# Sheet1.net
KiCad netlist of a schematic drawn in Altium Designer
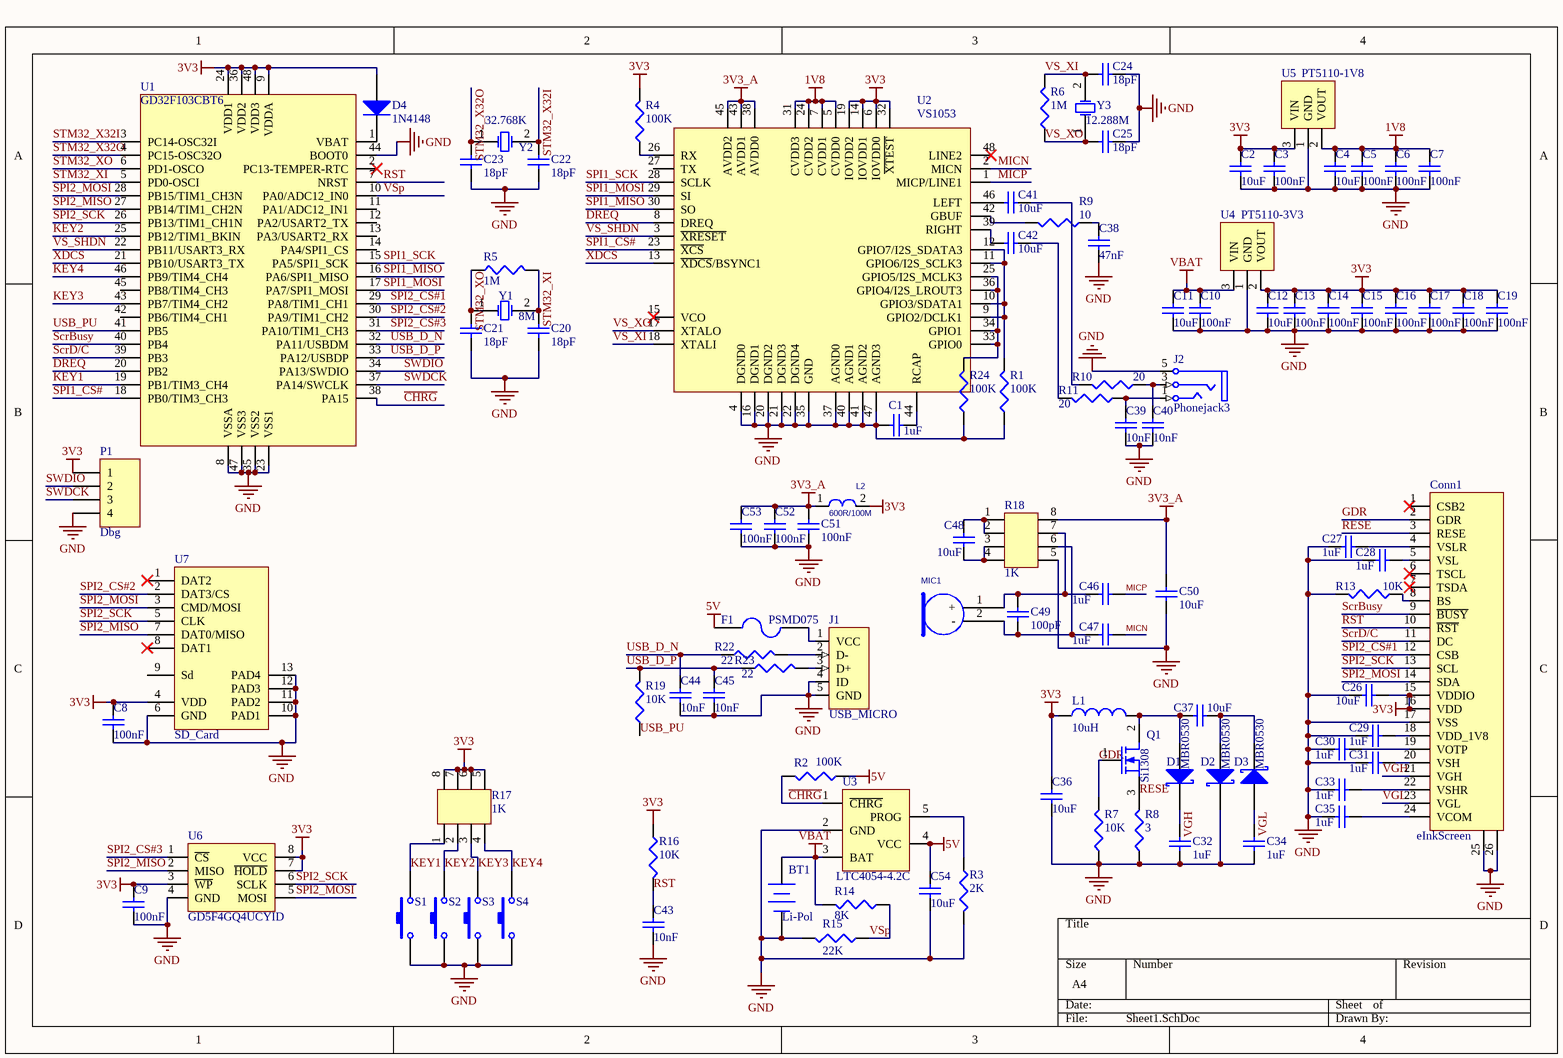
[diagram p0: Sheet1.SchDoc]

(export (version "E")
  (design (tool "Eeschema 10.0.6"))
  (components
    (comp (ref "BT1")
      (value "Li-Pol")
      (footprint "BAT-2")
      (description "Multicell Battery")
      (fields (field (name "PUBLISHER") "Altium Limited"))
      (libsource (lib "Miscellaneous Devices") (part "Battery"))
    )
    (comp (ref "C1")
      (value "1uF")
      (footprint "0603C")
      (description "Capacitor")
      (fields (field (name "Comment") "Cap") (field (name "PUBLISHER") "Altium Limited"))
      (libsource (lib "Miscellaneous Devices") (part "Cap"))
    )
    (comp (ref "C2")
      (value "10uF")
      (footprint "0603C")
      (description "Capacitor")
      (fields (field (name "Comment") "Cap") (field (name "PUBLISHER") "Altium Limited"))
      (libsource (lib "Miscellaneous Devices") (part "Cap"))
    )
    (comp (ref "C3")
      (value "100nF")
      (footprint "0603C")
      (description "Capacitor")
      (fields (field (name "Comment") "Cap") (field (name "PUBLISHER") "Altium Limited"))
      (libsource (lib "Miscellaneous Devices") (part "Cap"))
    )
    (comp (ref "C4")
      (value "10uF")
      (footprint "0603C")
      (description "Capacitor")
      (fields (field (name "Comment") "Cap") (field (name "PUBLISHER") "Altium Limited"))
      (libsource (lib "Miscellaneous Devices") (part "Cap"))
    )
    (comp (ref "C5")
      (value "100nF")
      (footprint "0603C")
      (description "Capacitor")
      (fields (field (name "Comment") "Cap") (field (name "PUBLISHER") "Altium Limited"))
      (libsource (lib "Miscellaneous Devices") (part "Cap"))
    )
    (comp (ref "C6")
      (value "100nF")
      (footprint "0603C")
      (description "Capacitor")
      (fields (field (name "Comment") "Cap") (field (name "PUBLISHER") "Altium Limited"))
      (libsource (lib "Miscellaneous Devices") (part "Cap"))
    )
    (comp (ref "C7")
      (value "100nF")
      (footprint "0603C")
      (description "Capacitor")
      (fields (field (name "Comment") "Cap") (field (name "PUBLISHER") "Altium Limited"))
      (libsource (lib "Miscellaneous Devices") (part "Cap"))
    )
    (comp (ref "C8")
      (value "100nF")
      (footprint "0603C")
      (description "Capacitor")
      (fields (field (name "Comment") "Cap") (field (name "PUBLISHER") "Altium Limited"))
      (libsource (lib "Miscellaneous Devices") (part "Cap"))
    )
    (comp (ref "C9")
      (value "100nF")
      (footprint "0603C")
      (description "Capacitor")
      (fields (field (name "Comment") "Cap") (field (name "PUBLISHER") "Altium Limited"))
      (libsource (lib "Miscellaneous Devices") (part "Cap"))
    )
    (comp (ref "C10")
      (value "100nF")
      (footprint "0603C")
      (description "Capacitor")
      (fields (field (name "Comment") "Cap") (field (name "PUBLISHER") "Altium Limited"))
      (libsource (lib "Miscellaneous Devices") (part "Cap"))
    )
    (comp (ref "C11")
      (value "10uF")
      (footprint "0603C")
      (description "Capacitor")
      (fields (field (name "Comment") "Cap") (field (name "PUBLISHER") "Altium Limited"))
      (libsource (lib "Miscellaneous Devices") (part "Cap"))
    )
    (comp (ref "C12")
      (value "10uF")
      (footprint "0603C")
      (description "Capacitor")
      (fields (field (name "Comment") "Cap") (field (name "PUBLISHER") "Altium Limited"))
      (libsource (lib "Miscellaneous Devices") (part "Cap"))
    )
    (comp (ref "C13")
      (value "100nF")
      (footprint "0603C")
      (description "Capacitor")
      (fields (field (name "Comment") "Cap") (field (name "PUBLISHER") "Altium Limited"))
      (libsource (lib "Miscellaneous Devices") (part "Cap"))
    )
    (comp (ref "C14")
      (value "100nF")
      (footprint "0603C")
      (description "Capacitor")
      (fields (field (name "Comment") "Cap") (field (name "PUBLISHER") "Altium Limited"))
      (libsource (lib "Miscellaneous Devices") (part "Cap"))
    )
    (comp (ref "C15")
      (value "100nF")
      (footprint "0603C")
      (description "Capacitor")
      (fields (field (name "Comment") "Cap") (field (name "PUBLISHER") "Altium Limited"))
      (libsource (lib "Miscellaneous Devices") (part "Cap"))
    )
    (comp (ref "C16")
      (value "100nF")
      (footprint "0603C")
      (description "Capacitor")
      (fields (field (name "Comment") "Cap") (field (name "PUBLISHER") "Altium Limited"))
      (libsource (lib "Miscellaneous Devices") (part "Cap"))
    )
    (comp (ref "C17")
      (value "100nF")
      (footprint "0603C")
      (description "Capacitor")
      (fields (field (name "Comment") "Cap") (field (name "PUBLISHER") "Altium Limited"))
      (libsource (lib "Miscellaneous Devices") (part "Cap"))
    )
    (comp (ref "C18")
      (value "100nF")
      (footprint "0603C")
      (description "Capacitor")
      (fields (field (name "Comment") "Cap") (field (name "PUBLISHER") "Altium Limited"))
      (libsource (lib "Miscellaneous Devices") (part "Cap"))
    )
    (comp (ref "C19")
      (value "100nF")
      (footprint "0603C")
      (description "Capacitor")
      (fields (field (name "Comment") "Cap") (field (name "PUBLISHER") "Altium Limited"))
      (libsource (lib "Miscellaneous Devices") (part "Cap"))
    )
    (comp (ref "C20")
      (value "18pF")
      (footprint "0603C")
      (description "Capacitor")
      (fields (field (name "Comment") "Cap") (field (name "PUBLISHER") "Altium Limited"))
      (libsource (lib "Miscellaneous Devices") (part "Cap"))
    )
    (comp (ref "C21")
      (value "18pF")
      (footprint "0603C")
      (description "Capacitor")
      (fields (field (name "Comment") "Cap") (field (name "PUBLISHER") "Altium Limited"))
      (libsource (lib "Miscellaneous Devices") (part "Cap"))
    )
    (comp (ref "C22")
      (value "18pF")
      (footprint "0603C")
      (description "Capacitor")
      (fields (field (name "Comment") "Cap") (field (name "PUBLISHER") "Altium Limited"))
      (libsource (lib "Miscellaneous Devices") (part "Cap"))
    )
    (comp (ref "C23")
      (value "18pF")
      (footprint "0603C")
      (description "Capacitor")
      (fields (field (name "Comment") "Cap") (field (name "PUBLISHER") "Altium Limited"))
      (libsource (lib "Miscellaneous Devices") (part "Cap"))
    )
    (comp (ref "C24")
      (value "18pF")
      (footprint "0603C")
      (description "Capacitor")
      (fields (field (name "Comment") "Cap") (field (name "PUBLISHER") "Altium Limited"))
      (libsource (lib "Miscellaneous Devices") (part "Cap"))
    )
    (comp (ref "C25")
      (value "18pF")
      (footprint "0603C")
      (description "Capacitor")
      (fields (field (name "Comment") "Cap") (field (name "PUBLISHER") "Altium Limited"))
      (libsource (lib "Miscellaneous Devices") (part "Cap"))
    )
    (comp (ref "C26")
      (value "10uF")
      (footprint "0603C")
      (description "Capacitor")
      (fields (field (name "Comment") "Cap") (field (name "PUBLISHER") "Altium Limited"))
      (libsource (lib "Miscellaneous Devices") (part "Cap"))
    )
    (comp (ref "C27")
      (value "1uF")
      (footprint "0603C")
      (description "Capacitor")
      (fields (field (name "Comment") "Cap") (field (name "PUBLISHER") "Altium Limited"))
      (libsource (lib "Miscellaneous Devices") (part "Cap"))
    )
    (comp (ref "C28")
      (value "1uF")
      (footprint "0603C")
      (description "Capacitor")
      (fields (field (name "Comment") "Cap") (field (name "PUBLISHER") "Altium Limited"))
      (libsource (lib "Miscellaneous Devices") (part "Cap"))
    )
    (comp (ref "C29")
      (value "1uF")
      (footprint "0603C")
      (description "Capacitor")
      (fields (field (name "Comment") "Cap") (field (name "PUBLISHER") "Altium Limited"))
      (libsource (lib "Miscellaneous Devices") (part "Cap"))
    )
    (comp (ref "C30")
      (value "1uF")
      (footprint "0603C")
      (description "Capacitor")
      (fields (field (name "Comment") "Cap") (field (name "PUBLISHER") "Altium Limited"))
      (libsource (lib "Miscellaneous Devices") (part "Cap"))
    )
    (comp (ref "C31")
      (value "1uF")
      (footprint "0603C")
      (description "Capacitor")
      (fields (field (name "Comment") "Cap") (field (name "PUBLISHER") "Altium Limited"))
      (libsource (lib "Miscellaneous Devices") (part "Cap"))
    )
    (comp (ref "C32")
      (value "1uF")
      (footprint "0603C")
      (description "Capacitor")
      (fields (field (name "Comment") "Cap") (field (name "PUBLISHER") "Altium Limited"))
      (libsource (lib "Miscellaneous Devices") (part "Cap"))
    )
    (comp (ref "C33")
      (value "1uF")
      (footprint "0603C")
      (description "Capacitor")
      (fields (field (name "Comment") "Cap") (field (name "PUBLISHER") "Altium Limited"))
      (libsource (lib "Miscellaneous Devices") (part "Cap"))
    )
    (comp (ref "C34")
      (value "1uF")
      (footprint "0603C")
      (description "Capacitor")
      (fields (field (name "Comment") "Cap") (field (name "PUBLISHER") "Altium Limited"))
      (libsource (lib "Miscellaneous Devices") (part "Cap"))
    )
    (comp (ref "C35")
      (value "1uF")
      (footprint "0603C")
      (description "Capacitor")
      (fields (field (name "Comment") "Cap") (field (name "PUBLISHER") "Altium Limited"))
      (libsource (lib "Miscellaneous Devices") (part "Cap"))
    )
    (comp (ref "C36")
      (value "10uF")
      (footprint "0603C")
      (description "Capacitor")
      (fields (field (name "Comment") "Cap") (field (name "PUBLISHER") "Altium Limited"))
      (libsource (lib "Miscellaneous Devices") (part "Cap"))
    )
    (comp (ref "C37")
      (value "10uF")
      (footprint "0603C")
      (description "Capacitor")
      (fields (field (name "Comment") "Cap") (field (name "PUBLISHER") "Altium Limited"))
      (libsource (lib "Miscellaneous Devices") (part "Cap"))
    )
    (comp (ref "C38")
      (value "47nF")
      (footprint "0603C")
      (description "Capacitor")
      (fields (field (name "Comment") "Cap") (field (name "PUBLISHER") "Altium Limited"))
      (libsource (lib "Miscellaneous Devices") (part "Cap"))
    )
    (comp (ref "C39")
      (value "10nF")
      (footprint "0603C")
      (description "Capacitor")
      (fields (field (name "Comment") "Cap") (field (name "PUBLISHER") "Altium Limited"))
      (libsource (lib "Miscellaneous Devices") (part "Cap"))
    )
    (comp (ref "C40")
      (value "10nF")
      (footprint "0603C")
      (description "Capacitor")
      (fields (field (name "Comment") "Cap") (field (name "PUBLISHER") "Altium Limited"))
      (libsource (lib "Miscellaneous Devices") (part "Cap"))
    )
    (comp (ref "C41")
      (value "10uF")
      (footprint "0603C")
      (description "Capacitor")
      (fields (field (name "Comment") "Cap") (field (name "PUBLISHER") "Altium Limited"))
      (libsource (lib "Miscellaneous Devices") (part "Cap"))
    )
    (comp (ref "C42")
      (value "10uF")
      (footprint "0603C")
      (description "Capacitor")
      (fields (field (name "Comment") "Cap") (field (name "PUBLISHER") "Altium Limited"))
      (libsource (lib "Miscellaneous Devices") (part "Cap"))
    )
    (comp (ref "C43")
      (value "10nF")
      (footprint "0603C")
      (description "Capacitor")
      (fields (field (name "Comment") "Cap") (field (name "PUBLISHER") "Altium Limited"))
      (libsource (lib "Miscellaneous Devices") (part "Cap"))
    )
    (comp (ref "C44")
      (value "10nF")
      (footprint "0603C")
      (description "Capacitor")
      (fields (field (name "Comment") "Cap") (field (name "PUBLISHER") "Altium Limited"))
      (libsource (lib "Miscellaneous Devices") (part "Cap"))
    )
    (comp (ref "C45")
      (value "10nF")
      (footprint "0603C")
      (description "Capacitor")
      (fields (field (name "Comment") "Cap") (field (name "PUBLISHER") "Altium Limited"))
      (libsource (lib "Miscellaneous Devices") (part "Cap"))
    )
    (comp (ref "C46")
      (value "1uF")
      (footprint "0603C")
      (description "Capacitor")
      (fields (field (name "Comment") "Cap") (field (name "PUBLISHER") "Altium Limited"))
      (libsource (lib "Miscellaneous Devices") (part "Cap"))
    )
    (comp (ref "C47")
      (value "1uF")
      (footprint "0603C")
      (description "Capacitor")
      (fields (field (name "Comment") "Cap") (field (name "PUBLISHER") "Altium Limited"))
      (libsource (lib "Miscellaneous Devices") (part "Cap"))
    )
    (comp (ref "C48")
      (value "10uF")
      (footprint "0603C")
      (description "Capacitor")
      (fields (field (name "Comment") "Cap") (field (name "PUBLISHER") "Altium Limited"))
      (libsource (lib "Miscellaneous Devices") (part "Cap"))
    )
    (comp (ref "C49")
      (value "100pF")
      (footprint "0603C")
      (description "Capacitor")
      (fields (field (name "Comment") "Cap") (field (name "PUBLISHER") "Altium Limited"))
      (libsource (lib "Miscellaneous Devices") (part "Cap"))
    )
    (comp (ref "C50")
      (value "10uF")
      (footprint "0603C")
      (description "Capacitor")
      (fields (field (name "Comment") "Cap") (field (name "PUBLISHER") "Altium Limited"))
      (libsource (lib "Miscellaneous Devices") (part "Cap"))
    )
    (comp (ref "C51")
      (value "100nF")
      (footprint "0603C")
      (description "Capacitor")
      (fields (field (name "Comment") "Cap") (field (name "PUBLISHER") "Altium Limited"))
      (libsource (lib "Miscellaneous Devices") (part "Cap"))
    )
    (comp (ref "C52")
      (value "100nF")
      (footprint "0603C")
      (description "Capacitor")
      (fields (field (name "Comment") "Cap") (field (name "PUBLISHER") "Altium Limited"))
      (libsource (lib "Miscellaneous Devices") (part "Cap"))
    )
    (comp (ref "C53")
      (value "100nF")
      (footprint "0603C")
      (description "Capacitor")
      (fields (field (name "Comment") "Cap") (field (name "PUBLISHER") "Altium Limited"))
      (libsource (lib "Miscellaneous Devices") (part "Cap"))
    )
    (comp (ref "C54")
      (value "10uF")
      (footprint "0603C")
      (description "Capacitor")
      (fields (field (name "Comment") "Cap") (field (name "PUBLISHER") "Altium Limited"))
      (libsource (lib "Miscellaneous Devices") (part "Cap"))
    )
    (comp (ref "Conn1")
      (value "eInkScreen")
      (footprint "FPC-24P-0.5")
      (libsource (lib "STM32") (part "eINK_FPC24"))
    )
    (comp (ref "D1")
      (value "MBR0530")
      (footprint "SOD123")
      (description "Schottky Diode")
      (fields (field (name "PUBLISHER") "Altium Limited"))
      (libsource (lib "Miscellaneous Devices") (part "D Schottky"))
    )
    (comp (ref "D2")
      (value "MBR0530")
      (footprint "SOD123")
      (description "Schottky Diode")
      (fields (field (name "PUBLISHER") "Altium Limited"))
      (libsource (lib "Miscellaneous Devices") (part "D Schottky"))
    )
    (comp (ref "D3")
      (value "MBR0530")
      (footprint "SOD123")
      (description "Schottky Diode")
      (fields (field (name "PUBLISHER") "Altium Limited"))
      (libsource (lib "Miscellaneous Devices") (part "D Schottky"))
    )
    (comp (ref "D4")
      (value "1N4148")
      (footprint "0805LED2")
      (description "High Conductance Fast Diode")
      (fields (field (name "PUBLISHER") "Altium Limited"))
      (libsource (lib "Miscellaneous Devices") (part "Diode 1N4148"))
    )
    (comp (ref "F1")
      (value "PSMD075")
      (footprint "0805-1R")
      (description "Fuse")
      (fields (field (name "PUBLISHER") "Altium Limited"))
      (libsource (lib "Miscellaneous Devices") (part "Fuse 2"))
    )
    (comp (ref "J1")
      (value "USB_MICRO")
      (footprint "MicroUSB")
      (libsource (lib "PublicSch") (part "USB_MICRO"))
    )
    (comp (ref "J2")
      (value "Phonejack3")
      (footprint "PJ-320B")
      (description "Jack Socket, 1/4\" [6.5mm], Thru-Hole, Vertical, 3-Conductor Open Circuit (Non-Normalling)")
      (fields (field (name "PUBLISHER") "Altium Limited"))
      (libsource (lib "Miscellaneous Connectors") (part "Phonejack3"))
    )
    (comp (ref "L1")
      (value "10uH")
      (footprint "1210R")
      (description "Inductor")
      (fields (field (name "PUBLISHER") "Altium Limited"))
      (libsource (lib "Miscellaneous Devices") (part "Inductor"))
    )
    (comp (ref "L2")
      (value "600R/100M")
      (footprint "L0603")
      (description "RoHS BEAD/600ohm 100Mhz Z=600Ω DCR<0.2Ω 800mA SMT L0603")
      (libsource (lib "*") (part "INDUCTOR_0_Dup1"))
    )
    (comp (ref "MIC1") (value "Micphone") (footprint "mic_4015") (libsource (lib "*") (part "Micphone_0")))
    (comp (ref "P1")
      (value "Dbg")
      (footprint "HDR1X4")
      (description "Header, 4-Pin")
      (fields (field (name "PUBLISHER") "Altium Limited"))
      (libsource (lib "Miscellaneous Connectors") (part "Header 4"))
    )
    (comp (ref "Q1") (value "Si1308") (footprint "SOT323-N") (libsource (lib "PowerChips") (part "PwrMOS_N")))
    (comp (ref "R1")
      (value "100K")
      (footprint "0603R")
      (description "Resistor")
      (fields (field (name "Comment") "Res3") (field (name "PUBLISHER") "Altium Limited"))
      (libsource (lib "Miscellaneous Devices") (part "Res3"))
    )
    (comp (ref "R2")
      (value "100K")
      (footprint "0603R")
      (description "Resistor")
      (fields (field (name "Comment") "Res3") (field (name "PUBLISHER") "Altium Limited"))
      (libsource (lib "Miscellaneous Devices") (part "Res3"))
    )
    (comp (ref "R3")
      (value "2K")
      (footprint "0603R")
      (description "Resistor")
      (fields (field (name "Comment") "Res3") (field (name "PUBLISHER") "Altium Limited"))
      (libsource (lib "Miscellaneous Devices") (part "Res3"))
    )
    (comp (ref "R4")
      (value "100K")
      (footprint "0603R")
      (description "Resistor")
      (fields (field (name "Comment") "Res3") (field (name "PUBLISHER") "Altium Limited"))
      (libsource (lib "Miscellaneous Devices") (part "Res3"))
    )
    (comp (ref "R5")
      (value "1M")
      (footprint "0603R")
      (description "Resistor")
      (fields (field (name "Comment") "Res3") (field (name "PUBLISHER") "Altium Limited"))
      (libsource (lib "Miscellaneous Devices") (part "Res3"))
    )
    (comp (ref "R6")
      (value "1M")
      (footprint "0603R")
      (description "Resistor")
      (fields (field (name "Comment") "Res3") (field (name "PUBLISHER") "Altium Limited"))
      (libsource (lib "Miscellaneous Devices") (part "Res3"))
    )
    (comp (ref "R7")
      (value "10K")
      (footprint "0603R")
      (description "Resistor")
      (fields (field (name "Comment") "Res3") (field (name "PUBLISHER") "Altium Limited"))
      (libsource (lib "Miscellaneous Devices") (part "Res3"))
    )
    (comp (ref "R8")
      (value "3")
      (footprint "0603R")
      (description "Resistor")
      (fields (field (name "Comment") "Res3") (field (name "PUBLISHER") "Altium Limited"))
      (libsource (lib "Miscellaneous Devices") (part "Res3"))
    )
    (comp (ref "R9")
      (value "10")
      (footprint "0603R")
      (description "Resistor")
      (fields (field (name "Comment") "Res3") (field (name "PUBLISHER") "Altium Limited"))
      (libsource (lib "Miscellaneous Devices") (part "Res3"))
    )
    (comp (ref "R10")
      (value "20")
      (footprint "0603R")
      (description "Resistor")
      (fields (field (name "Comment") "Res3") (field (name "PUBLISHER") "Altium Limited"))
      (libsource (lib "Miscellaneous Devices") (part "Res3"))
    )
    (comp (ref "R11")
      (value "20")
      (footprint "0603R")
      (description "Resistor")
      (fields (field (name "Comment") "Res3") (field (name "PUBLISHER") "Altium Limited"))
      (libsource (lib "Miscellaneous Devices") (part "Res3"))
    )
    (comp (ref "R13")
      (value "10K")
      (footprint "0603R")
      (description "Resistor")
      (fields (field (name "Comment") "Res3") (field (name "PUBLISHER") "Altium Limited"))
      (libsource (lib "Miscellaneous Devices") (part "Res3"))
    )
    (comp (ref "R14")
      (value "8K")
      (footprint "0603R")
      (description "Resistor")
      (fields (field (name "Comment") "Res3") (field (name "PUBLISHER") "Altium Limited"))
      (libsource (lib "Miscellaneous Devices") (part "Res3"))
    )
    (comp (ref "R15")
      (value "22K")
      (footprint "0603R")
      (description "Resistor")
      (fields (field (name "Comment") "Res3") (field (name "PUBLISHER") "Altium Limited"))
      (libsource (lib "Miscellaneous Devices") (part "Res3"))
    )
    (comp (ref "R16")
      (value "10K")
      (footprint "0603R")
      (description "Resistor")
      (fields (field (name "Comment") "Res3") (field (name "PUBLISHER") "Altium Limited"))
      (libsource (lib "Miscellaneous Devices") (part "Res3"))
    )
    (comp (ref "R17") (value "1K") (footprint "YC164") (libsource (lib "") (part "ResPak-8P4R_1")))
    (comp (ref "R18") (value "1K") (footprint "YC164") (libsource (lib "PublicSch") (part "ResPak-8P4R")))
    (comp (ref "R19")
      (value "10K")
      (footprint "0603R")
      (description "Resistor")
      (fields (field (name "Comment") "Res3") (field (name "PUBLISHER") "Altium Limited"))
      (libsource (lib "Miscellaneous Devices") (part "Res3"))
    )
    (comp (ref "R22")
      (value "22")
      (footprint "0603R")
      (description "Resistor")
      (fields (field (name "Comment") "Res3") (field (name "PUBLISHER") "Altium Limited"))
      (libsource (lib "Miscellaneous Devices") (part "Res3"))
    )
    (comp (ref "R23")
      (value "22")
      (footprint "0603R")
      (description "Resistor")
      (fields (field (name "Comment") "Res3") (field (name "PUBLISHER") "Altium Limited"))
      (libsource (lib "Miscellaneous Devices") (part "Res3"))
    )
    (comp (ref "R24")
      (value "100K")
      (footprint "0603R")
      (description "Resistor")
      (fields (field (name "Comment") "Res3") (field (name "PUBLISHER") "Altium Limited"))
      (libsource (lib "Miscellaneous Devices") (part "Res3"))
    )
    (comp (ref "S1")
      (value "SW-PB")
      (footprint "SPST-2")
      (description "Switch")
      (fields (field (name "PUBLISHER") "Altium Limited"))
      (libsource (lib "Miscellaneous Devices") (part "SW-PB"))
    )
    (comp (ref "S2")
      (value "SW-PB")
      (footprint "SPST-2")
      (description "Switch")
      (fields (field (name "PUBLISHER") "Altium Limited"))
      (libsource (lib "Miscellaneous Devices") (part "SW-PB"))
    )
    (comp (ref "S3")
      (value "SW-PB")
      (footprint "SPST-2")
      (description "Switch")
      (fields (field (name "PUBLISHER") "Altium Limited"))
      (libsource (lib "Miscellaneous Devices") (part "SW-PB"))
    )
    (comp (ref "S4")
      (value "SW-PB")
      (footprint "SPST-2")
      (description "Switch")
      (fields (field (name "PUBLISHER") "Altium Limited"))
      (libsource (lib "Miscellaneous Devices") (part "SW-PB"))
    )
    (comp (ref "U1")
      (value "GD32F103CBT6")
      (footprint "LQFP48-7x7")
      (libsource (lib "STM32") (part "STM32F103CxT6"))
    )
    (comp (ref "U2") (value "VS1053") (footprint "LQFP48-7x7") (libsource (lib "STM32") (part "VS1053")))
    (comp (ref "U3")
      (value "LTC4054-4.2C")
      (footprint "SOT23-5")
      (libsource (lib "PowerChips") (part "LTC4054"))
    )
    (comp (ref "U4") (value "PT5110-3V3") (footprint "SOT23") (libsource (lib "PowerChips") (part "PT5110")))
    (comp (ref "U5") (value "PT5110-1V8") (footprint "SOT23") (libsource (lib "PowerChips") (part "PT5110")))
    (comp (ref "U6")
      (value "GD5F4GQ4UCYID")
      (footprint "TSOP8+WSON8-6X5")
      (libsource (lib "Stroage") (part "W25Qxx"))
    )
    (comp (ref "U7")
      (value "SD_Card")
      (footprint "TF_self-eject")
      (libsource (lib "Stroage") (part "SD_Card"))
    )
    (comp (ref "Y1")
      (value "8M")
      (footprint "XTAL-5032")
      (description "Crystal Oscillator")
      (fields (field (name "PUBLISHER") "Altium Limited"))
      (libsource (lib "Miscellaneous Devices") (part "XTAL"))
    )
    (comp (ref "Y2")
      (value "32.768K")
      (footprint "XTAL-3215")
      (description "Crystal Oscillator")
      (fields (field (name "PUBLISHER") "Altium Limited"))
      (libsource (lib "Miscellaneous Devices") (part "XTAL"))
    )
    (comp (ref "Y3")
      (value "12.288M")
      (footprint "XTAL-5032")
      (description "Crystal Oscillator")
      (fields (field (name "PUBLISHER") "Altium Limited"))
      (libsource (lib "Miscellaneous Devices") (part "XTAL"))
    )
  )
  (nets
    (net (code "1") (name "/DREQ") (class "Default")
      (node (ref "U1") (pin "20") (pinfunction "PB2_20") (pintype "passive"))
      (node (ref "U2") (pin "8") (pinfunction "DREQ_8") (pintype "power_in"))
    )
    (net (code "2") (name "/GDR") (class "Default")
      (node (ref "Conn1") (pin "2") (pinfunction "GDR_2") (pintype "power_in"))
      (node (ref "Q1") (pin "1") (pinfunction "G_1") (pintype "passive"))
      (node (ref "R7") (pin "2") (pinfunction "2_2") (pintype "passive"))
    )
    (net (code "3") (name "/KEY1") (class "Default")
      (node (ref "R17") (pin "1") (pinfunction "1_1") (pintype "passive"))
      (node (ref "S1") (pin "2") (pinfunction "2_2") (pintype "passive"))
      (node (ref "U1") (pin "19") (pinfunction "PB1/TIM3_CH4_19") (pintype "passive"))
    )
    (net (code "4") (name "/KEY2") (class "Default")
      (node (ref "R17") (pin "2") (pinfunction "2_2") (pintype "passive"))
      (node (ref "S2") (pin "2") (pinfunction "2_2") (pintype "passive"))
      (node (ref "U1") (pin "25") (pinfunction "PB12/TIM1_BKIN_25") (pintype "passive"))
    )
    (net (code "5") (name "/KEY3") (class "Default")
      (node (ref "R17") (pin "3") (pinfunction "3_3") (pintype "passive"))
      (node (ref "S3") (pin "2") (pinfunction "2_2") (pintype "passive"))
      (node (ref "U1") (pin "43") (pinfunction "PB7/TIM4_CH2_43") (pintype "passive"))
    )
    (net (code "6") (name "/KEY4") (class "Default")
      (node (ref "R17") (pin "4") (pinfunction "4_4") (pintype "passive"))
      (node (ref "S4") (pin "2") (pinfunction "2_2") (pintype "passive"))
      (node (ref "U1") (pin "46") (pinfunction "PB9/TIM4_CH4_46") (pintype "passive"))
    )
    (net (code "7") (name "/MICN") (class "Default")
      (node (ref "C47") (pin "1") (pinfunction "1_1") (pintype "passive"))
      (node (ref "U2") (pin "2") (pinfunction "MICN_2") (pintype "power_in"))
    )
    (net (code "8") (name "/MICP") (class "Default")
      (node (ref "C46") (pin "1") (pinfunction "1_1") (pintype "passive"))
      (node (ref "U2") (pin "1") (pinfunction "MICP/LINE1_1") (pintype "power_in"))
    )
    (net (code "9") (name "/RESE") (class "Default")
      (node (ref "Conn1") (pin "3") (pinfunction "RESE_3") (pintype "power_in"))
      (node (ref "Q1") (pin "3") (pinfunction "3_3") (pintype "passive"))
      (node (ref "R8") (pin "2") (pinfunction "2_2") (pintype "passive"))
    )
    (net (code "10") (name "/RST") (class "Default")
      (node (ref "C43") (pin "2") (pinfunction "2_2") (pintype "passive"))
      (node (ref "Conn1") (pin "10") (pinfunction "~{RST}_10") (pintype "power_in"))
      (node (ref "R16") (pin "2") (pinfunction "2_2") (pintype "passive"))
      (node (ref "U1") (pin "7") (pinfunction "NRST_7") (pintype "passive"))
    )
    (net (code "11") (name "/SPI1_CS#") (class "Default")
      (node (ref "U1") (pin "18") (pinfunction "PB0/TIM3_CH3_18") (pintype "passive"))
      (node (ref "U2") (pin "23") (pinfunction "~{XCS}_23") (pintype "power_in"))
    )
    (net (code "12") (name "/SPI1_MISO") (class "Default")
      (node (ref "U1") (pin "16") (pinfunction "PA6/SPI1_MISO_16") (pintype "passive"))
      (node (ref "U2") (pin "30") (pinfunction "SO_30") (pintype "power_in"))
    )
    (net (code "13") (name "/SPI1_MOSI") (class "Default")
      (node (ref "U1") (pin "17") (pinfunction "PA7/SPI1_MOSI_17") (pintype "passive"))
      (node (ref "U2") (pin "29") (pinfunction "SI_29") (pintype "power_in"))
    )
    (net (code "14") (name "/SPI1_SCK") (class "Default")
      (node (ref "U1") (pin "15") (pinfunction "PA5/SPI1_SCK_15") (pintype "passive"))
      (node (ref "U2") (pin "28") (pinfunction "SCLK_28") (pintype "power_in"))
    )
    (net (code "15") (name "/SPI2_CS#1") (class "Default")
      (node (ref "Conn1") (pin "12") (pinfunction "CSB_12") (pintype "power_in"))
      (node (ref "U1") (pin "29") (pinfunction "PA8/TIM1_CH1_29") (pintype "passive"))
    )
    (net (code "16") (name "/SPI2_CS#2") (class "Default")
      (node (ref "U1") (pin "30") (pinfunction "PA9/TIM1_CH2_30") (pintype "passive"))
      (node (ref "U7") (pin "2") (pinfunction "DAT3/CS_2") (pintype "passive"))
    )
    (net (code "17") (name "/SPI2_CS#3") (class "Default")
      (node (ref "U1") (pin "31") (pinfunction "PA10/TIM1_CH3_31") (pintype "passive"))
      (node (ref "U6") (pin "1") (pinfunction "~{CS}_1") (pintype "passive"))
    )
    (net (code "18") (name "/SPI2_MISO") (class "Default")
      (node (ref "U1") (pin "27") (pinfunction "PB14/TIM1_CH2N_27") (pintype "passive"))
      (node (ref "U6") (pin "2") (pinfunction "MISO_2") (pintype "passive"))
      (node (ref "U7") (pin "7") (pinfunction "DAT0/MISO_7") (pintype "passive"))
    )
    (net (code "19") (name "/SPI2_MOSI") (class "Default")
      (node (ref "Conn1") (pin "14") (pinfunction "SDA_14") (pintype "power_in"))
      (node (ref "U1") (pin "28") (pinfunction "PB15/TIM1_CH3N_28") (pintype "passive"))
      (node (ref "U6") (pin "5") (pinfunction "MOSI_5") (pintype "passive"))
      (node (ref "U7") (pin "3") (pinfunction "CMD/MOSI_3") (pintype "passive"))
    )
    (net (code "20") (name "/SPI2_SCK") (class "Default")
      (node (ref "Conn1") (pin "13") (pinfunction "SCL_13") (pintype "power_in"))
      (node (ref "U1") (pin "26") (pinfunction "PB13/TIM1_CH1N_26") (pintype "passive"))
      (node (ref "U6") (pin "6") (pinfunction "SCLK_6") (pintype "passive"))
      (node (ref "U7") (pin "5") (pinfunction "CLK_5") (pintype "passive"))
    )
    (net (code "21") (name "/STM32_X32I") (class "Default")
      (node (ref "C22") (pin "1") (pinfunction "1_1") (pintype "passive"))
      (node (ref "U1") (pin "3") (pinfunction "PC14-OSC32I_3") (pintype "passive"))
      (node (ref "Y2") (pin "2") (pinfunction "OSC2_2") (pintype "passive"))
    )
    (net (code "22") (name "/STM32_X32O") (class "Default")
      (node (ref "C23") (pin "1") (pinfunction "1_1") (pintype "passive"))
      (node (ref "U1") (pin "4") (pinfunction "PC15-OSC32O_4") (pintype "passive"))
      (node (ref "Y2") (pin "1") (pinfunction "OSC1_1") (pintype "passive"))
    )
    (net (code "23") (name "/STM32_XI") (class "Default")
      (node (ref "C20") (pin "1") (pinfunction "1_1") (pintype "passive"))
      (node (ref "R5") (pin "2") (pinfunction "2_2") (pintype "passive"))
      (node (ref "U1") (pin "5") (pinfunction "PD0-OSCI_5") (pintype "passive"))
      (node (ref "Y1") (pin "2") (pinfunction "OSC2_2") (pintype "passive"))
    )
    (net (code "24") (name "/STM32_XO") (class "Default")
      (node (ref "C21") (pin "1") (pinfunction "1_1") (pintype "passive"))
      (node (ref "R5") (pin "1") (pinfunction "1_1") (pintype "passive"))
      (node (ref "U1") (pin "6") (pinfunction "PD1-OSCO_6") (pintype "passive"))
      (node (ref "Y1") (pin "1") (pinfunction "OSC1_1") (pintype "passive"))
    )
    (net (code "25") (name "/SWDCK") (class "Default")
      (node (ref "P1") (pin "3") (pinfunction "3_3") (pintype "passive"))
      (node (ref "U1") (pin "37") (pinfunction "PA14/SWCLK_37") (pintype "passive"))
    )
    (net (code "26") (name "/SWDIO") (class "Default")
      (node (ref "P1") (pin "2") (pinfunction "2_2") (pintype "passive"))
      (node (ref "U1") (pin "34") (pinfunction "PA13/SWDIO_34") (pintype "passive"))
    )
    (net (code "27") (name "/ScrBusy") (class "Default")
      (node (ref "Conn1") (pin "9") (pinfunction "~{BUSY}_9") (pintype "power_in"))
      (node (ref "U1") (pin "40") (pinfunction "PB4_40") (pintype "passive"))
    )
    (net (code "28") (name "/ScrD{slash}C") (class "Default")
      (node (ref "Conn1") (pin "11") (pinfunction "DC_11") (pintype "power_in"))
      (node (ref "U1") (pin "39") (pinfunction "PB3_39") (pintype "passive"))
    )
    (net (code "29") (name "/USB_D_N") (class "Default")
      (node (ref "C44") (pin "2") (pinfunction "2_2") (pintype "passive"))
      (node (ref "R22") (pin "1") (pinfunction "1_1") (pintype "passive"))
      (node (ref "U1") (pin "32") (pinfunction "PA11/USBDM_32") (pintype "passive"))
    )
    (net (code "30") (name "/USB_D_P") (class "Default")
      (node (ref "C45") (pin "2") (pinfunction "2_2") (pintype "passive"))
      (node (ref "R19") (pin "2") (pinfunction "2_2") (pintype "passive"))
      (node (ref "R23") (pin "1") (pinfunction "1_1") (pintype "passive"))
      (node (ref "U1") (pin "33") (pinfunction "PA12/USBDP_33") (pintype "passive"))
    )
    (net (code "31") (name "/USB_PU") (class "Default")
      (node (ref "R19") (pin "1") (pinfunction "1_1") (pintype "passive"))
      (node (ref "U1") (pin "41") (pinfunction "PB5_41") (pintype "passive"))
    )
    (net (code "32") (name "/VGH") (class "Default")
      (node (ref "C32") (pin "2") (pinfunction "2_2") (pintype "passive"))
      (node (ref "Conn1") (pin "21") (pinfunction "VGH_21") (pintype "power_in"))
      (node (ref "D1") (pin "2") (pinfunction "K_2") (pintype "passive"))
    )
    (net (code "33") (name "/VGL") (class "Default")
      (node (ref "C34") (pin "2") (pinfunction "2_2") (pintype "passive"))
      (node (ref "Conn1") (pin "23") (pinfunction "VGL_23") (pintype "power_in"))
      (node (ref "D3") (pin "1") (pinfunction "A_1") (pintype "passive"))
    )
    (net (code "34") (name "/VS_SHDN") (class "Default")
      (node (ref "U1") (pin "22") (pinfunction "PB11/USART3_RX_22") (pintype "passive"))
      (node (ref "U2") (pin "3") (pinfunction "~{XRESET}_3") (pintype "power_in"))
    )
    (net (code "35") (name "/VS_XI") (class "Default")
      (node (ref "C24") (pin "1") (pinfunction "1_1") (pintype "passive"))
      (node (ref "R6") (pin "2") (pinfunction "2_2") (pintype "passive"))
      (node (ref "U2") (pin "18") (pinfunction "XTALI_18") (pintype "power_in"))
      (node (ref "Y3") (pin "2") (pinfunction "OSC2_2") (pintype "passive"))
    )
    (net (code "36") (name "/VS_XO") (class "Default")
      (node (ref "C25") (pin "1") (pinfunction "1_1") (pintype "passive"))
      (node (ref "R6") (pin "1") (pinfunction "1_1") (pintype "passive"))
      (node (ref "U2") (pin "17") (pinfunction "XTALO_17") (pintype "power_in"))
      (node (ref "Y3") (pin "1") (pinfunction "OSC1_1") (pintype "passive"))
    )
    (net (code "37") (name "/VSp") (class "Default")
      (node (ref "R14") (pin "1") (pinfunction "1_1") (pintype "passive"))
      (node (ref "R15") (pin "1") (pinfunction "1_1") (pintype "passive"))
      (node (ref "U1") (pin "10") (pinfunction "PA0/ADC12_IN0_10") (pintype "passive"))
    )
    (net (code "38") (name "/XDCS") (class "Default")
      (node (ref "U1") (pin "21") (pinfunction "PB10/USART3_TX_21") (pintype "passive"))
      (node (ref "U2") (pin "13") (pinfunction "~{XDCS}/BSYNC1_13") (pintype "power_in"))
    )
    (net (code "39") (name "/~{CHRG}") (class "Default")
      (node (ref "R2") (pin "2") (pinfunction "2_2") (pintype "passive"))
      (node (ref "U1") (pin "38") (pinfunction "PA15_38") (pintype "passive"))
      (node (ref "U3") (pin "1") (pinfunction "~{CHRG}_1") (pintype "power_in"))
    )
    (net (code "40") (name "1V8") (class "Default")
      (node (ref "C4") (pin "1") (pinfunction "1_1") (pintype "passive"))
      (node (ref "C5") (pin "1") (pinfunction "1_1") (pintype "passive"))
      (node (ref "C6") (pin "1") (pinfunction "1_1") (pintype "passive"))
      (node (ref "C7") (pin "1") (pinfunction "1_1") (pintype "passive"))
      (node (ref "U2") (pin "24") (pinfunction "CVDD2_24") (pintype "power_in"))
      (node (ref "U2") (pin "31") (pinfunction "CVDD3_31") (pintype "power_in"))
      (node (ref "U2") (pin "5") (pinfunction "CVDD0_5") (pintype "power_in"))
      (node (ref "U2") (pin "7") (pinfunction "CVDD1_7") (pintype "power_in"))
      (node (ref "U5") (pin "2") (pinfunction "VOUT_2") (pintype "power_in"))
    )
    (net (code "41") (name "3V3") (class "Default")
      (node (ref "C12") (pin "2") (pinfunction "2_2") (pintype "passive"))
      (node (ref "C13") (pin "2") (pinfunction "2_2") (pintype "passive"))
      (node (ref "C14") (pin "2") (pinfunction "2_2") (pintype "passive"))
      (node (ref "C15") (pin "2") (pinfunction "2_2") (pintype "passive"))
      (node (ref "C16") (pin "2") (pinfunction "2_2") (pintype "passive"))
      (node (ref "C17") (pin "2") (pinfunction "2_2") (pintype "passive"))
      (node (ref "C18") (pin "2") (pinfunction "2_2") (pintype "passive"))
      (node (ref "C19") (pin "2") (pinfunction "2_2") (pintype "passive"))
      (node (ref "C2") (pin "1") (pinfunction "1_1") (pintype "passive"))
      (node (ref "C26") (pin "2") (pinfunction "2_2") (pintype "passive"))
      (node (ref "C3") (pin "1") (pinfunction "1_1") (pintype "passive"))
      (node (ref "C36") (pin "2") (pinfunction "2_2") (pintype "passive"))
      (node (ref "C8") (pin "1") (pinfunction "1_1") (pintype "passive"))
      (node (ref "C9") (pin "2") (pinfunction "2_2") (pintype "passive"))
      (node (ref "Conn1") (pin "15") (pinfunction "VDDIO_15") (pintype "power_in"))
      (node (ref "Conn1") (pin "16") (pinfunction "VDD_16") (pintype "power_in"))
      (node (ref "D4") (pin "1") (pinfunction "A_1") (pintype "passive"))
      (node (ref "L1") (pin "1") (pinfunction "1_1") (pintype "passive"))
      (node (ref "L2") (pin "2") (pinfunction "2_2") (pintype "passive"))
      (node (ref "P1") (pin "1") (pinfunction "1_1") (pintype "passive"))
      (node (ref "R16") (pin "1") (pinfunction "1_1") (pintype "passive"))
      (node (ref "R17") (pin "5") (pinfunction "5_5") (pintype "passive"))
      (node (ref "R17") (pin "6") (pinfunction "6_6") (pintype "passive"))
      (node (ref "R17") (pin "7") (pinfunction "7_7") (pintype "passive"))
      (node (ref "R17") (pin "8") (pinfunction "8_8") (pintype "passive"))
      (node (ref "R4") (pin "2") (pinfunction "2_2") (pintype "passive"))
      (node (ref "U1") (pin "24") (pinfunction "VDD1_24") (pintype "passive"))
      (node (ref "U1") (pin "36") (pinfunction "VDD2_36") (pintype "passive"))
      (node (ref "U1") (pin "48") (pinfunction "VDD3_48") (pintype "passive"))
      (node (ref "U1") (pin "9") (pinfunction "VDDA_9") (pintype "passive"))
      (node (ref "U2") (pin "14") (pinfunction "IOVDD1_14") (pintype "power_in"))
      (node (ref "U2") (pin "19") (pinfunction "IOVDD2_19") (pintype "power_in"))
      (node (ref "U2") (pin "32") (pinfunction "~{XTEST}_32") (pintype "power_in"))
      (node (ref "U2") (pin "6") (pinfunction "IOVDD0_6") (pintype "power_in"))
      (node (ref "U4") (pin "2") (pinfunction "VOUT_2") (pintype "power_in"))
      (node (ref "U5") (pin "3") (pinfunction "VIN_3") (pintype "power_in"))
      (node (ref "U6") (pin "3") (pinfunction "~{WP}_3") (pintype "passive"))
      (node (ref "U6") (pin "7") (pinfunction "~{HOLD}_7") (pintype "passive"))
      (node (ref "U6") (pin "8") (pinfunction "VCC_8") (pintype "passive"))
      (node (ref "U7") (pin "4") (pinfunction "VDD_4") (pintype "passive"))
    )
    (net (code "42") (name "3V3_A") (class "Default")
      (node (ref "C50") (pin "2") (pinfunction "2_2") (pintype "passive"))
      (node (ref "C51") (pin "2") (pinfunction "2_2") (pintype "passive"))
      (node (ref "C52") (pin "2") (pinfunction "2_2") (pintype "passive"))
      (node (ref "C53") (pin "2") (pinfunction "2_2") (pintype "passive"))
      (node (ref "L2") (pin "1") (pinfunction "1_1") (pintype "passive"))
      (node (ref "R18") (pin "8") (pinfunction "8_8") (pintype "passive"))
      (node (ref "U2") (pin "38") (pinfunction "AVDD0_38") (pintype "power_in"))
      (node (ref "U2") (pin "43") (pinfunction "AVDD1_43") (pintype "power_in"))
      (node (ref "U2") (pin "45") (pinfunction "AVDD2_45") (pintype "power_in"))
    )
    (net (code "43") (name "5V") (class "Default")
      (node (ref "C54") (pin "2") (pinfunction "2_2") (pintype "passive"))
      (node (ref "F1") (pin "1") (pinfunction "1_1") (pintype "passive"))
      (node (ref "R2") (pin "1") (pinfunction "1_1") (pintype "passive"))
      (node (ref "U3") (pin "4") (pinfunction "VCC_4") (pintype "power_in"))
    )
    (net (code "44") (name "GND") (class "Default")
      (node (ref "BT1") (pin "2") (pinfunction "-_2") (pintype "passive"))
      (node (ref "C1") (pin "1") (pinfunction "1_1") (pintype "passive"))
      (node (ref "C10") (pin "1") (pinfunction "1_1") (pintype "passive"))
      (node (ref "C11") (pin "1") (pinfunction "1_1") (pintype "passive"))
      (node (ref "C12") (pin "1") (pinfunction "1_1") (pintype "passive"))
      (node (ref "C13") (pin "1") (pinfunction "1_1") (pintype "passive"))
      (node (ref "C14") (pin "1") (pinfunction "1_1") (pintype "passive"))
      (node (ref "C15") (pin "1") (pinfunction "1_1") (pintype "passive"))
      (node (ref "C16") (pin "1") (pinfunction "1_1") (pintype "passive"))
      (node (ref "C17") (pin "1") (pinfunction "1_1") (pintype "passive"))
      (node (ref "C18") (pin "1") (pinfunction "1_1") (pintype "passive"))
      (node (ref "C19") (pin "1") (pinfunction "1_1") (pintype "passive"))
      (node (ref "C2") (pin "2") (pinfunction "2_2") (pintype "passive"))
      (node (ref "C20") (pin "2") (pinfunction "2_2") (pintype "passive"))
      (node (ref "C21") (pin "2") (pinfunction "2_2") (pintype "passive"))
      (node (ref "C22") (pin "2") (pinfunction "2_2") (pintype "passive"))
      (node (ref "C23") (pin "2") (pinfunction "2_2") (pintype "passive"))
      (node (ref "C24") (pin "2") (pinfunction "2_2") (pintype "passive"))
      (node (ref "C25") (pin "2") (pinfunction "2_2") (pintype "passive"))
      (node (ref "C26") (pin "1") (pinfunction "1_1") (pintype "passive"))
      (node (ref "C27") (pin "1") (pinfunction "1_1") (pintype "passive"))
      (node (ref "C28") (pin "1") (pinfunction "1_1") (pintype "passive"))
      (node (ref "C29") (pin "1") (pinfunction "1_1") (pintype "passive"))
      (node (ref "C3") (pin "2") (pinfunction "2_2") (pintype "passive"))
      (node (ref "C30") (pin "1") (pinfunction "1_1") (pintype "passive"))
      (node (ref "C31") (pin "1") (pinfunction "1_1") (pintype "passive"))
      (node (ref "C32") (pin "1") (pinfunction "1_1") (pintype "passive"))
      (node (ref "C33") (pin "1") (pinfunction "1_1") (pintype "passive"))
      (node (ref "C34") (pin "1") (pinfunction "1_1") (pintype "passive"))
      (node (ref "C35") (pin "1") (pinfunction "1_1") (pintype "passive"))
      (node (ref "C36") (pin "1") (pinfunction "1_1") (pintype "passive"))
      (node (ref "C38") (pin "1") (pinfunction "1_1") (pintype "passive"))
      (node (ref "C39") (pin "1") (pinfunction "1_1") (pintype "passive"))
      (node (ref "C4") (pin "2") (pinfunction "2_2") (pintype "passive"))
      (node (ref "C40") (pin "1") (pinfunction "1_1") (pintype "passive"))
      (node (ref "C43") (pin "1") (pinfunction "1_1") (pintype "passive"))
      (node (ref "C44") (pin "1") (pinfunction "1_1") (pintype "passive"))
      (node (ref "C45") (pin "1") (pinfunction "1_1") (pintype "passive"))
      (node (ref "C5") (pin "2") (pinfunction "2_2") (pintype "passive"))
      (node (ref "C50") (pin "1") (pinfunction "1_1") (pintype "passive"))
      (node (ref "C51") (pin "1") (pinfunction "1_1") (pintype "passive"))
      (node (ref "C52") (pin "1") (pinfunction "1_1") (pintype "passive"))
      (node (ref "C53") (pin "1") (pinfunction "1_1") (pintype "passive"))
      (node (ref "C54") (pin "1") (pinfunction "1_1") (pintype "passive"))
      (node (ref "C6") (pin "2") (pinfunction "2_2") (pintype "passive"))
      (node (ref "C7") (pin "2") (pinfunction "2_2") (pintype "passive"))
      (node (ref "C8") (pin "2") (pinfunction "2_2") (pintype "passive"))
      (node (ref "C9") (pin "1") (pinfunction "1_1") (pintype "passive"))
      (node (ref "Conn1") (pin "17") (pinfunction "VSS_17") (pintype "power_in"))
      (node (ref "Conn1") (pin "25") (pinfunction "25_25") (pintype "power_in"))
      (node (ref "Conn1") (pin "26") (pinfunction "26_26") (pintype "power_in"))
      (node (ref "D2") (pin "2") (pinfunction "K_2") (pintype "passive"))
      (node (ref "J1") (pin "4") (pinfunction "ID_4") (pintype "power_in"))
      (node (ref "J1") (pin "5") (pinfunction "GND_5") (pintype "power_in"))
      (node (ref "J2") (pin "5") (pinfunction "S_5") (pintype "power_in"))
      (node (ref "P1") (pin "4") (pinfunction "4_4") (pintype "passive"))
      (node (ref "R1") (pin "1") (pinfunction "1_1") (pintype "passive"))
      (node (ref "R13") (pin "2") (pinfunction "2_2") (pintype "passive"))
      (node (ref "R15") (pin "2") (pinfunction "2_2") (pintype "passive"))
      (node (ref "R18") (pin "5") (pinfunction "5_5") (pintype "passive"))
      (node (ref "R24") (pin "1") (pinfunction "1_1") (pintype "passive"))
      (node (ref "R3") (pin "2") (pinfunction "2_2") (pintype "passive"))
      (node (ref "R7") (pin "1") (pinfunction "1_1") (pintype "passive"))
      (node (ref "R8") (pin "1") (pinfunction "1_1") (pintype "passive"))
      (node (ref "S1") (pin "1") (pinfunction "1_1") (pintype "passive"))
      (node (ref "S2") (pin "1") (pinfunction "1_1") (pintype "passive"))
      (node (ref "S3") (pin "1") (pinfunction "1_1") (pintype "passive"))
      (node (ref "S4") (pin "1") (pinfunction "1_1") (pintype "passive"))
      (node (ref "U1") (pin "23") (pinfunction "VSS1_23") (pintype "passive"))
      (node (ref "U1") (pin "35") (pinfunction "VSS2_35") (pintype "passive"))
      (node (ref "U1") (pin "44") (pinfunction "BOOT0_44") (pintype "passive"))
      (node (ref "U1") (pin "47") (pinfunction "VSS3_47") (pintype "passive"))
      (node (ref "U1") (pin "8") (pinfunction "VSSA_8") (pintype "passive"))
      (node (ref "U2") (pin "16") (pinfunction "DGND1_16") (pintype "power_in"))
      (node (ref "U2") (pin "20") (pinfunction "DGND2_20") (pintype "power_in"))
      (node (ref "U2") (pin "21") (pinfunction "DGND3_21") (pintype "power_in"))
      (node (ref "U2") (pin "22") (pinfunction "DGND4_22") (pintype "power_in"))
      (node (ref "U2") (pin "35") (pinfunction "GND_35") (pintype "power_in"))
      (node (ref "U2") (pin "37") (pinfunction "AGND0_37") (pintype "power_in"))
      (node (ref "U2") (pin "4") (pinfunction "DGND0_4") (pintype "power_in"))
      (node (ref "U2") (pin "40") (pinfunction "AGND1_40") (pintype "power_in"))
      (node (ref "U2") (pin "41") (pinfunction "AGND2_41") (pintype "power_in"))
      (node (ref "U2") (pin "47") (pinfunction "AGND3_47") (pintype "power_in"))
      (node (ref "U3") (pin "2") (pinfunction "GND_2") (pintype "power_in"))
      (node (ref "U4") (pin "1") (pinfunction "GND_1") (pintype "power_in"))
      (node (ref "U5") (pin "1") (pinfunction "GND_1") (pintype "power_in"))
      (node (ref "U6") (pin "4") (pinfunction "GND_4") (pintype "passive"))
      (node (ref "U7") (pin "10") (pinfunction "PAD1_10") (pintype "passive"))
      (node (ref "U7") (pin "11") (pinfunction "PAD2_11") (pintype "passive"))
      (node (ref "U7") (pin "12") (pinfunction "PAD3_12") (pintype "passive"))
      (node (ref "U7") (pin "13") (pinfunction "PAD4_13") (pintype "passive"))
      (node (ref "U7") (pin "6") (pinfunction "GND_6") (pintype "passive"))
    )
    (net (code "45") (name "Net-(C38-Pad2)") (class "Default")
      (node (ref "C38") (pin "2") (pinfunction "2_2") (pintype "passive"))
      (node (ref "R9") (pin "1") (pinfunction "1_1") (pintype "passive"))
    )
    (net (code "46") (name "Net-(C41-Pad1)") (class "Default")
      (node (ref "C41") (pin "1") (pinfunction "1_1") (pintype "passive"))
      (node (ref "R10") (pin "2") (pinfunction "2_2") (pintype "passive"))
    )
    (net (code "47") (name "Net-(C42-Pad1)") (class "Default")
      (node (ref "C42") (pin "1") (pinfunction "1_1") (pintype "passive"))
      (node (ref "R11") (pin "2") (pinfunction "2_2") (pintype "passive"))
    )
    (net (code "48") (name "Net-(C48-Pad1)") (class "Default")
      (node (ref "C48") (pin "1") (pinfunction "1_1") (pintype "passive"))
      (node (ref "R18") (pin "3") (pinfunction "3_3") (pintype "passive"))
      (node (ref "R18") (pin "4") (pinfunction "4_4") (pintype "passive"))
    )
    (net (code "49") (name "Net-(C48-Pad2)") (class "Default")
      (node (ref "C48") (pin "2") (pinfunction "2_2") (pintype "passive"))
      (node (ref "R18") (pin "1") (pinfunction "1_1") (pintype "passive"))
      (node (ref "R18") (pin "2") (pinfunction "2_2") (pintype "passive"))
    )
    (net (code "50") (name "Net-(Conn1-BS)") (class "Default")
      (node (ref "Conn1") (pin "8") (pinfunction "BS_8") (pintype "power_in"))
      (node (ref "R13") (pin "1") (pinfunction "1_1") (pintype "passive"))
    )
    (net (code "51") (name "Net-(Conn1-VCOM)") (class "Default")
      (node (ref "C35") (pin "2") (pinfunction "2_2") (pintype "passive"))
      (node (ref "Conn1") (pin "24") (pinfunction "VCOM_24") (pintype "power_in"))
    )
    (net (code "52") (name "Net-(Conn1-VDD_1V8)") (class "Default")
      (node (ref "C29") (pin "2") (pinfunction "2_2") (pintype "passive"))
      (node (ref "Conn1") (pin "18") (pinfunction "VDD_1V8_18") (pintype "power_in"))
    )
    (net (code "53") (name "Net-(Conn1-VOTP)") (class "Default")
      (node (ref "C30") (pin "2") (pinfunction "2_2") (pintype "passive"))
      (node (ref "Conn1") (pin "19") (pinfunction "VOTP_19") (pintype "power_in"))
    )
    (net (code "54") (name "Net-(Conn1-VSH)") (class "Default")
      (node (ref "C31") (pin "2") (pinfunction "2_2") (pintype "passive"))
      (node (ref "Conn1") (pin "20") (pinfunction "VSH_20") (pintype "power_in"))
    )
    (net (code "55") (name "Net-(Conn1-VSHR)") (class "Default")
      (node (ref "C33") (pin "2") (pinfunction "2_2") (pintype "passive"))
      (node (ref "Conn1") (pin "22") (pinfunction "VSHR_22") (pintype "power_in"))
    )
    (net (code "56") (name "Net-(Conn1-VSL)") (class "Default")
      (node (ref "C28") (pin "2") (pinfunction "2_2") (pintype "passive"))
      (node (ref "Conn1") (pin "5") (pinfunction "VSL_5") (pintype "power_in"))
    )
    (net (code "57") (name "Net-(Conn1-VSLR)") (class "Default")
      (node (ref "C27") (pin "2") (pinfunction "2_2") (pintype "passive"))
      (node (ref "Conn1") (pin "4") (pinfunction "VSLR_4") (pintype "power_in"))
    )
    (net (code "58") (name "Net-(D1-A)") (class "Default")
      (node (ref "C37") (pin "2") (pinfunction "2_2") (pintype "passive"))
      (node (ref "D1") (pin "1") (pinfunction "A_1") (pintype "passive"))
      (node (ref "L1") (pin "2") (pinfunction "2_2") (pintype "passive"))
      (node (ref "Q1") (pin "2") (pinfunction "2_2") (pintype "passive"))
    )
    (net (code "59") (name "Net-(D2-A)") (class "Default")
      (node (ref "C37") (pin "1") (pinfunction "1_1") (pintype "passive"))
      (node (ref "D2") (pin "1") (pinfunction "A_1") (pintype "passive"))
      (node (ref "D3") (pin "2") (pinfunction "K_2") (pintype "passive"))
    )
    (net (code "60") (name "Net-(D4-K)") (class "Default")
      (node (ref "D4") (pin "2") (pinfunction "K_2") (pintype "passive"))
      (node (ref "U1") (pin "1") (pinfunction "VBAT_1") (pintype "passive"))
    )
    (net (code "61") (name "Net-(J1-D+)") (class "Default")
      (node (ref "J1") (pin "3") (pinfunction "D+_3") (pintype "input"))
      (node (ref "R23") (pin "2") (pinfunction "2_2") (pintype "passive"))
    )
    (net (code "62") (name "Net-(J1-D-)") (class "Default")
      (node (ref "J1") (pin "2") (pinfunction "D-_2") (pintype "input"))
      (node (ref "R22") (pin "2") (pinfunction "2_2") (pintype "passive"))
    )
    (net (code "63") (name "Net-(J1-VCC)") (class "Default")
      (node (ref "F1") (pin "2") (pinfunction "2_2") (pintype "passive"))
      (node (ref "J1") (pin "1") (pinfunction "VCC_1") (pintype "power_in"))
    )
    (net (code "64") (name "Net-(J2-R)") (class "Default")
      (node (ref "C40") (pin "2") (pinfunction "2_2") (pintype "passive"))
      (node (ref "J2") (pin "3") (pinfunction "R_3") (pintype "input"))
      (node (ref "R10") (pin "1") (pinfunction "1_1") (pintype "passive"))
    )
    (net (code "65") (name "Net-(J2-T)") (class "Default")
      (node (ref "C39") (pin "2") (pinfunction "2_2") (pintype "passive"))
      (node (ref "J2") (pin "1") (pinfunction "T_1") (pintype "input"))
      (node (ref "R11") (pin "1") (pinfunction "1_1") (pintype "passive"))
    )
    (net (code "66") (name "Net-(MIC1-+)") (class "Default")
      (node (ref "C46") (pin "2") (pinfunction "2_2") (pintype "passive"))
      (node (ref "C49") (pin "2") (pinfunction "2_2") (pintype "passive"))
      (node (ref "MIC1") (pin "1") (pinfunction "+_1") (pintype "passive"))
      (node (ref "R18") (pin "7") (pinfunction "7_7") (pintype "passive"))
    )
    (net (code "67") (name "Net-(MIC1--)") (class "Default")
      (node (ref "C47") (pin "2") (pinfunction "2_2") (pintype "passive"))
      (node (ref "C49") (pin "1") (pinfunction "1_1") (pintype "passive"))
      (node (ref "MIC1") (pin "2") (pinfunction "-_2") (pintype "passive"))
      (node (ref "R18") (pin "6") (pinfunction "6_6") (pintype "passive"))
    )
    (net (code "68") (name "Net-(U2-GBUF)") (class "Default")
      (node (ref "R9") (pin "2") (pinfunction "2_2") (pintype "passive"))
      (node (ref "U2") (pin "42") (pinfunction "GBUF_42") (pintype "power_in"))
    )
    (net (code "69") (name "Net-(U2-GPIO0)") (class "Default")
      (node (ref "R24") (pin "2") (pinfunction "2_2") (pintype "passive"))
      (node (ref "U2") (pin "25") (pinfunction "GPIO5/I2S_MCLK3_25") (pintype "power_in"))
      (node (ref "U2") (pin "33") (pinfunction "GPIO0_33") (pintype "power_in"))
      (node (ref "U2") (pin "34") (pinfunction "GPIO1_34") (pintype "power_in"))
      (node (ref "U2") (pin "36") (pinfunction "GPIO4/I2S_LROUT3_36") (pintype "power_in"))
    )
    (net (code "70") (name "Net-(U2-GPIO2{slash}DCLK1)") (class "Default")
      (node (ref "R1") (pin "2") (pinfunction "2_2") (pintype "passive"))
      (node (ref "U2") (pin "10") (pinfunction "GPIO3/SDATA1_10") (pintype "power_in"))
      (node (ref "U2") (pin "11") (pinfunction "GPIO6/I2S_SCLK3_11") (pintype "power_in"))
      (node (ref "U2") (pin "12") (pinfunction "GPIO7/I2S_SDATA3_12") (pintype "power_in"))
      (node (ref "U2") (pin "9") (pinfunction "GPIO2/DCLK1_9") (pintype "power_in"))
    )
    (net (code "71") (name "Net-(U2-LEFT)") (class "Default")
      (node (ref "C41") (pin "2") (pinfunction "2_2") (pintype "passive"))
      (node (ref "U2") (pin "46") (pinfunction "LEFT_46") (pintype "power_in"))
    )
    (net (code "72") (name "Net-(U2-RCAP)") (class "Default")
      (node (ref "C1") (pin "2") (pinfunction "2_2") (pintype "passive"))
      (node (ref "U2") (pin "44") (pinfunction "RCAP_44") (pintype "power_in"))
    )
    (net (code "73") (name "Net-(U2-RIGHT)") (class "Default")
      (node (ref "C42") (pin "2") (pinfunction "2_2") (pintype "passive"))
      (node (ref "U2") (pin "39") (pinfunction "RIGHT_39") (pintype "power_in"))
    )
    (net (code "74") (name "Net-(U2-RX)") (class "Default")
      (node (ref "R4") (pin "1") (pinfunction "1_1") (pintype "passive"))
      (node (ref "U2") (pin "26") (pinfunction "RX_26") (pintype "power_in"))
    )
    (net (code "75") (name "Net-(U3-PROG)") (class "Default")
      (node (ref "R3") (pin "1") (pinfunction "1_1") (pintype "passive"))
      (node (ref "U3") (pin "5") (pinfunction "PROG_5") (pintype "power_in"))
    )
    (net (code "76") (name "VBAT") (class "Default")
      (node (ref "BT1") (pin "1") (pinfunction "+_1") (pintype "passive"))
      (node (ref "C10") (pin "2") (pinfunction "2_2") (pintype "passive"))
      (node (ref "C11") (pin "2") (pinfunction "2_2") (pintype "passive"))
      (node (ref "R14") (pin "2") (pinfunction "2_2") (pintype "passive"))
      (node (ref "U3") (pin "3") (pinfunction "BAT_3") (pintype "power_in"))
      (node (ref "U4") (pin "3") (pinfunction "VIN_3") (pintype "power_in"))
    )
    (net (code "77") (name "unconnected-(Conn1-CSB2-Pad1)") (class "Default")
      (node (ref "Conn1") (pin "1") (pinfunction "CSB2_1") (pintype "power_in+no_connect"))
    )
    (net (code "78") (name "unconnected-(Conn1-TSCL-Pad6)") (class "Default")
      (node (ref "Conn1") (pin "6") (pinfunction "TSCL_6") (pintype "power_in+no_connect"))
    )
    (net (code "79") (name "unconnected-(Conn1-TSDA-Pad7)") (class "Default")
      (node (ref "Conn1") (pin "7") (pinfunction "TSDA_7") (pintype "power_in+no_connect"))
    )
    (net (code "80") (name "unconnected-(U1-PA1{slash}ADC12_IN1-Pad11)") (class "Default")
      (node (ref "U1") (pin "11") (pinfunction "PA1/ADC12_IN1_11") (pintype "passive"))
    )
    (net (code "81") (name "unconnected-(U1-PA2{slash}USART2_TX-Pad12)") (class "Default")
      (node (ref "U1") (pin "12") (pinfunction "PA2/USART2_TX_12") (pintype "passive"))
    )
    (net (code "82") (name "unconnected-(U1-PA3{slash}USART2_RX-Pad13)") (class "Default")
      (node (ref "U1") (pin "13") (pinfunction "PA3/USART2_RX_13") (pintype "passive"))
    )
    (net (code "83") (name "unconnected-(U1-PA4{slash}SPI1_CS-Pad14)") (class "Default")
      (node (ref "U1") (pin "14") (pinfunction "PA4/SPI1_CS_14") (pintype "passive"))
    )
    (net (code "84") (name "unconnected-(U1-PB6{slash}TIM4_CH1-Pad42)") (class "Default")
      (node (ref "U1") (pin "42") (pinfunction "PB6/TIM4_CH1_42") (pintype "passive"))
    )
    (net (code "85") (name "unconnected-(U1-PB8{slash}TIM4_CH3-Pad45)") (class "Default")
      (node (ref "U1") (pin "45") (pinfunction "PB8/TIM4_CH3_45") (pintype "passive"))
    )
    (net (code "86") (name "unconnected-(U1-PC13-TEMPER-RTC-Pad2)") (class "Default")
      (node (ref "U1") (pin "2") (pinfunction "PC13-TEMPER-RTC_2") (pintype "passive+no_connect"))
    )
    (net (code "87") (name "unconnected-(U2-LINE2-Pad48)") (class "Default")
      (node (ref "U2") (pin "48") (pinfunction "LINE2_48") (pintype "power_in+no_connect"))
    )
    (net (code "88") (name "unconnected-(U2-TX-Pad27)") (class "Default")
      (node (ref "U2") (pin "27") (pinfunction "TX_27") (pintype "power_in"))
    )
    (net (code "89") (name "unconnected-(U2-VCO-Pad15)") (class "Default")
      (node (ref "U2") (pin "15") (pinfunction "VCO_15") (pintype "power_in+no_connect"))
    )
    (net (code "90") (name "unconnected-(U7-DAT1-Pad8)") (class "Default")
      (node (ref "U7") (pin "8") (pinfunction "DAT1_8") (pintype "passive+no_connect"))
    )
    (net (code "91") (name "unconnected-(U7-DAT2-Pad1)") (class "Default")
      (node (ref "U7") (pin "1") (pinfunction "DAT2_1") (pintype "passive+no_connect"))
    )
    (net (code "92") (name "unconnected-(U7-Sd-Pad9)") (class "Default")
      (node (ref "U7") (pin "9") (pinfunction "Sd_9") (pintype "passive"))
    )
  )
)
